# CopernicusBasicTestCircuit.net
KiCad netlist of a schematic drawn in EAGLE
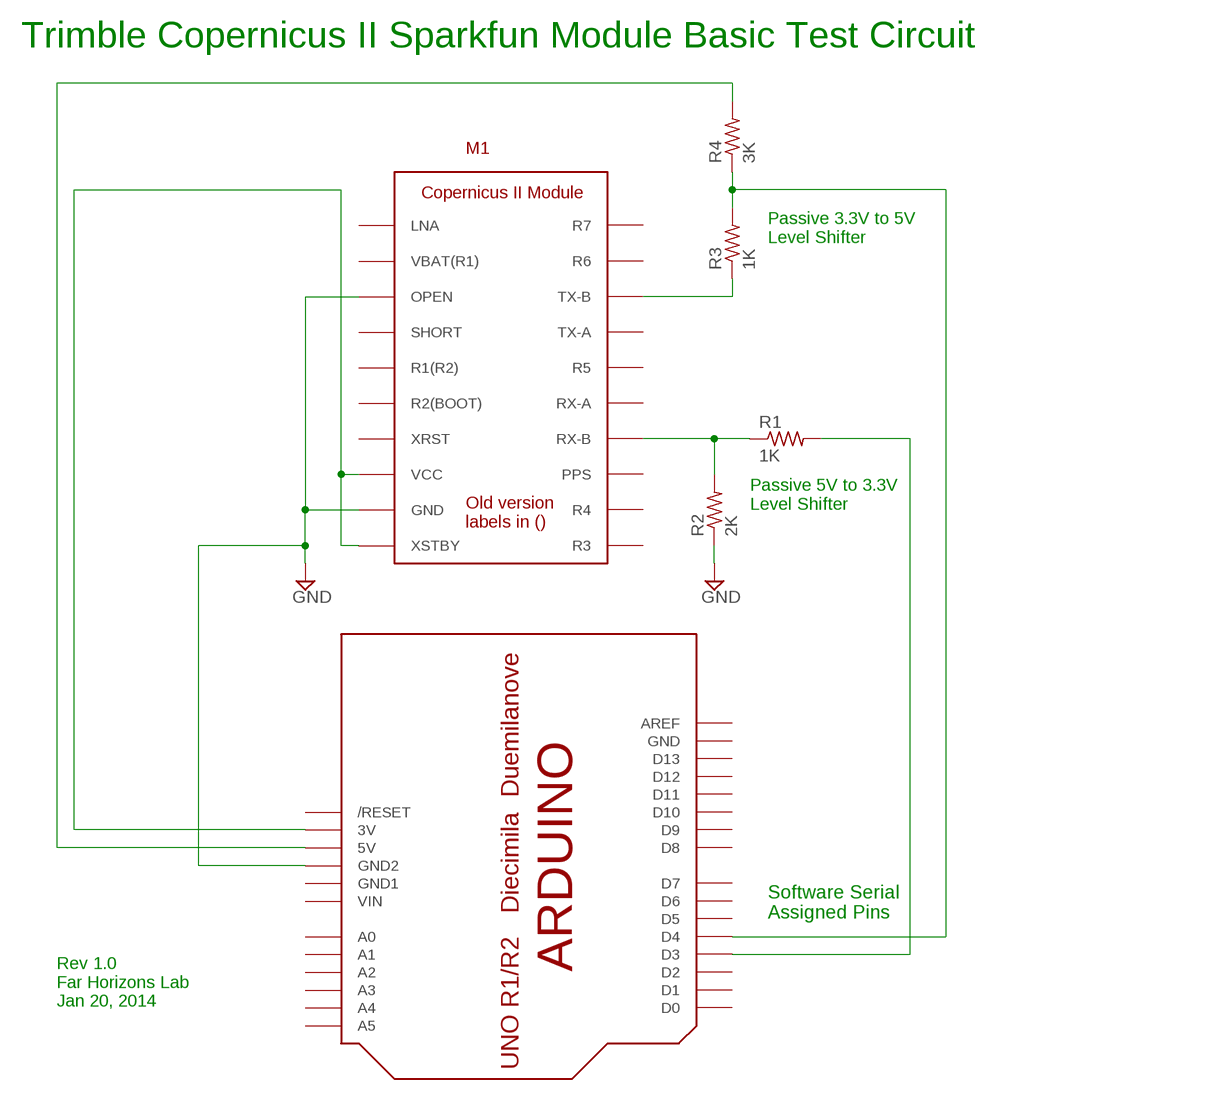
[diagram p0: schematic, sheet 1]

(export (version "E")
  (design (tool "Eeschema 10.0.6"))
  (components
    (comp (ref "M1")
      (value "COPERNICUS_II_MODULE")
      (footprint "eagle-import:COPERNICUS_II_MODULE")
      (libsource (lib "eagle-import") (part "COPERNICUS_II_MODULE"))
    )
    (comp (ref "R1")
      (value "1K")
      (footprint "eagle-import:0207_10")
      (libsource (lib "eagle-import") (part "R-US_0207/10"))
    )
    (comp (ref "R2")
      (value "2K")
      (footprint "eagle-import:0207_10")
      (libsource (lib "eagle-import") (part "R-US_0207/10"))
    )
    (comp (ref "R3")
      (value "1K")
      (footprint "eagle-import:0207_10")
      (libsource (lib "eagle-import") (part "R-US_0207/10"))
    )
    (comp (ref "R4")
      (value "3K")
      (footprint "eagle-import:0207_10")
      (libsource (lib "eagle-import") (part "R-US_0207/10"))
    )
    (comp (ref "U$1")
      (value "ARDUINOUNO")
      (footprint "eagle-import:ARDUINO")
      (libsource (lib "eagle-import") (part "ARDUINOUNO"))
    )
  )
  (nets
    (net (code "1") (name "GND") (class "Default")
      (node (ref "M1") (pin "P$3") (pinfunction "OPEN_P$3") (pintype "bidirectional"))
      (node (ref "M1") (pin "P$9") (pinfunction "GND_P$9") (pintype "bidirectional"))
      (node (ref "R2") (pin "1") (pinfunction "1_1") (pintype "passive"))
      (node (ref "U$1") (pin "GND2") (pinfunction "GND2_GND2") (pintype "bidirectional"))
    )
    (net (code "2") (name "Net-(M1-RX-B)") (class "Default")
      (node (ref "M1") (pin "P$14") (pinfunction "RX-B_P$14") (pintype "bidirectional"))
      (node (ref "R1") (pin "1") (pinfunction "1_1") (pintype "passive"))
      (node (ref "R2") (pin "2") (pinfunction "2_2") (pintype "passive"))
    )
    (net (code "3") (name "Net-(M1-TX-B)") (class "Default")
      (node (ref "M1") (pin "P$18") (pinfunction "TX-B_P$18") (pintype "bidirectional"))
      (node (ref "R3") (pin "1") (pinfunction "1_1") (pintype "passive"))
    )
    (net (code "4") (name "Net-(M1-VCC)") (class "Default")
      (node (ref "M1") (pin "P$10") (pinfunction "XSTBY_P$10") (pintype "bidirectional"))
      (node (ref "M1") (pin "P$8") (pinfunction "VCC_P$8") (pintype "bidirectional"))
      (node (ref "U$1") (pin "3V") (pinfunction "3V_3V") (pintype "output"))
    )
    (net (code "5") (name "Net-(R1-Pad2)") (class "Default")
      (node (ref "R1") (pin "2") (pinfunction "2_2") (pintype "passive"))
      (node (ref "U$1") (pin "D3") (pinfunction "D3_D3") (pintype "bidirectional"))
    )
    (net (code "6") (name "Net-(R3-Pad2)") (class "Default")
      (node (ref "R3") (pin "2") (pinfunction "2_2") (pintype "passive"))
      (node (ref "R4") (pin "1") (pinfunction "1_1") (pintype "passive"))
      (node (ref "U$1") (pin "D4") (pinfunction "D4_D4") (pintype "bidirectional"))
    )
    (net (code "7") (name "Net-(R4-Pad2)") (class "Default")
      (node (ref "R4") (pin "2") (pinfunction "2_2") (pintype "passive"))
      (node (ref "U$1") (pin "5V") (pinfunction "5V_5V") (pintype "output"))
    )
    (net (code "8") (name "unconnected-(M1-LNA-PadP$1)") (class "Default")
      (node (ref "M1") (pin "P$1") (pinfunction "LNA_P$1") (pintype "bidirectional"))
    )
    (net (code "9") (name "unconnected-(M1-PPS-PadP$13)") (class "Default")
      (node (ref "M1") (pin "P$13") (pinfunction "PPS_P$13") (pintype "bidirectional"))
    )
    (net (code "10") (name "unconnected-(M1-R1(R2)-PadP$5)") (class "Default")
      (node (ref "M1") (pin "P$5") (pinfunction "R1(R2)_P$5") (pintype "bidirectional"))
    )
    (net (code "11") (name "unconnected-(M1-R2(BOOT)-PadP$6)") (class "Default")
      (node (ref "M1") (pin "P$6") (pinfunction "R2(BOOT)_P$6") (pintype "bidirectional"))
    )
    (net (code "12") (name "unconnected-(M1-R3-PadP$11)") (class "Default")
      (node (ref "M1") (pin "P$11") (pinfunction "R3_P$11") (pintype "bidirectional"))
    )
    (net (code "13") (name "unconnected-(M1-R4-PadP$12)") (class "Default")
      (node (ref "M1") (pin "P$12") (pinfunction "R4_P$12") (pintype "bidirectional"))
    )
    (net (code "14") (name "unconnected-(M1-R5-PadP$16)") (class "Default")
      (node (ref "M1") (pin "P$16") (pinfunction "R5_P$16") (pintype "bidirectional"))
    )
    (net (code "15") (name "unconnected-(M1-R6-PadP$19)") (class "Default")
      (node (ref "M1") (pin "P$19") (pinfunction "R6_P$19") (pintype "bidirectional"))
    )
    (net (code "16") (name "unconnected-(M1-R7-PadP$20)") (class "Default")
      (node (ref "M1") (pin "P$20") (pinfunction "R7_P$20") (pintype "bidirectional"))
    )
    (net (code "17") (name "unconnected-(M1-RX-A-PadP$15)") (class "Default")
      (node (ref "M1") (pin "P$15") (pinfunction "RX-A_P$15") (pintype "bidirectional"))
    )
    (net (code "18") (name "unconnected-(M1-SHORT-PadP$4)") (class "Default")
      (node (ref "M1") (pin "P$4") (pinfunction "SHORT_P$4") (pintype "bidirectional"))
    )
    (net (code "19") (name "unconnected-(M1-TX-A-PadP$17)") (class "Default")
      (node (ref "M1") (pin "P$17") (pinfunction "TX-A_P$17") (pintype "bidirectional"))
    )
    (net (code "20") (name "unconnected-(M1-VBAT(R1)-PadP$2)") (class "Default")
      (node (ref "M1") (pin "P$2") (pinfunction "VBAT(R1)_P$2") (pintype "bidirectional"))
    )
    (net (code "21") (name "unconnected-(M1-XRST-PadP$7)") (class "Default")
      (node (ref "M1") (pin "P$7") (pinfunction "XRST_P$7") (pintype "bidirectional"))
    )
    (net (code "22") (name "unconnected-(U$1-PadA0)") (class "Default")
      (node (ref "U$1") (pin "A0") (pinfunction "A0_A0") (pintype "bidirectional"))
    )
    (net (code "23") (name "unconnected-(U$1-PadA1)") (class "Default")
      (node (ref "U$1") (pin "A1") (pinfunction "A1_A1") (pintype "bidirectional"))
    )
    (net (code "24") (name "unconnected-(U$1-PadA2)") (class "Default")
      (node (ref "U$1") (pin "A2") (pinfunction "A2_A2") (pintype "bidirectional"))
    )
    (net (code "25") (name "unconnected-(U$1-PadA3)") (class "Default")
      (node (ref "U$1") (pin "A3") (pinfunction "A3_A3") (pintype "bidirectional"))
    )
    (net (code "26") (name "unconnected-(U$1-PadA4)") (class "Default")
      (node (ref "U$1") (pin "A4") (pinfunction "A4_A4") (pintype "bidirectional"))
    )
    (net (code "27") (name "unconnected-(U$1-PadA5)") (class "Default")
      (node (ref "U$1") (pin "A5") (pinfunction "A5_A5") (pintype "bidirectional"))
    )
    (net (code "28") (name "unconnected-(U$1-PadAREF)") (class "Default")
      (node (ref "U$1") (pin "AREF") (pinfunction "AREF_AREF") (pintype "bidirectional"))
    )
    (net (code "29") (name "unconnected-(U$1-PadD0)") (class "Default")
      (node (ref "U$1") (pin "D0") (pinfunction "D0_D0") (pintype "bidirectional"))
    )
    (net (code "30") (name "unconnected-(U$1-PadD1)") (class "Default")
      (node (ref "U$1") (pin "D1") (pinfunction "D1_D1") (pintype "bidirectional"))
    )
    (net (code "31") (name "unconnected-(U$1-PadD2)") (class "Default")
      (node (ref "U$1") (pin "D2") (pinfunction "D2_D2") (pintype "bidirectional"))
    )
    (net (code "32") (name "unconnected-(U$1-PadD5)") (class "Default")
      (node (ref "U$1") (pin "D5") (pinfunction "D5_D5") (pintype "bidirectional"))
    )
    (net (code "33") (name "unconnected-(U$1-PadD6)") (class "Default")
      (node (ref "U$1") (pin "D6") (pinfunction "D6_D6") (pintype "bidirectional"))
    )
    (net (code "34") (name "unconnected-(U$1-PadD7)") (class "Default")
      (node (ref "U$1") (pin "D7") (pinfunction "D7_D7") (pintype "bidirectional"))
    )
    (net (code "35") (name "unconnected-(U$1-PadD8)") (class "Default")
      (node (ref "U$1") (pin "D8") (pinfunction "D8_D8") (pintype "bidirectional"))
    )
    (net (code "36") (name "unconnected-(U$1-PadD9)") (class "Default")
      (node (ref "U$1") (pin "D9") (pinfunction "D9_D9") (pintype "bidirectional"))
    )
    (net (code "37") (name "unconnected-(U$1-PadD10)") (class "Default")
      (node (ref "U$1") (pin "D10") (pinfunction "D10_D10") (pintype "bidirectional"))
    )
    (net (code "38") (name "unconnected-(U$1-PadD11)") (class "Default")
      (node (ref "U$1") (pin "D11") (pinfunction "D11_D11") (pintype "bidirectional"))
    )
    (net (code "39") (name "unconnected-(U$1-PadD12)") (class "Default")
      (node (ref "U$1") (pin "D12") (pinfunction "D12_D12") (pintype "bidirectional"))
    )
    (net (code "40") (name "unconnected-(U$1-PadD13)") (class "Default")
      (node (ref "U$1") (pin "D13") (pinfunction "D13_D13") (pintype "bidirectional"))
    )
    (net (code "41") (name "unconnected-(U$1-PadGND)") (class "Default")
      (node (ref "U$1") (pin "GND") (pinfunction "GND_GND") (pintype "bidirectional"))
    )
    (net (code "42") (name "unconnected-(U$1-PadGND1)") (class "Default")
      (node (ref "U$1") (pin "GND1") (pinfunction "GND1_GND1") (pintype "bidirectional"))
    )
    (net (code "43") (name "unconnected-(U$1-PadVIN)") (class "Default")
      (node (ref "U$1") (pin "VIN") (pinfunction "VIN_VIN") (pintype "bidirectional"))
    )
    (net (code "44") (name "unconnected-(U$1-{slash}RESET-PadRESET)") (class "Default")
      (node (ref "U$1") (pin "RESET") (pinfunction "/RESET_RESET") (pintype "bidirectional"))
    )
  )
)
